# omnetics_to_electrode.net
KiCad netlist of a schematic drawn in EAGLE
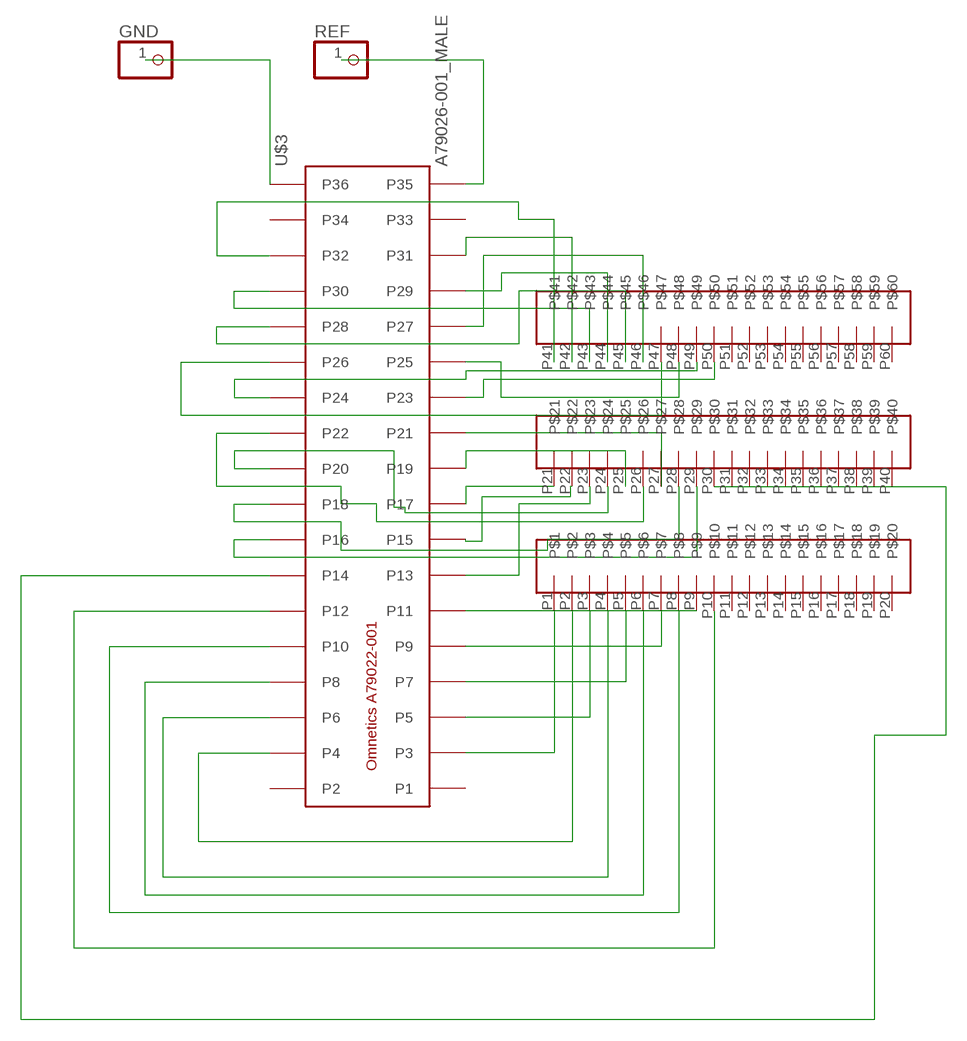
[diagram p0: schematic, sheet 1]

(export (version "E")
  (design (tool "Eeschema 10.0.6"))
  (components
    (comp (ref "GND")
      (value "PINHD-1X1")
      (footprint "eagle-import:1X01")
      (libsource (lib "eagle-import") (part "PINHD-1X1"))
    )
    (comp (ref "REF")
      (value "PINHD-1X1")
      (footprint "eagle-import:1X01")
      (libsource (lib "eagle-import") (part "PINHD-1X1"))
    )
    (comp (ref "U$1")
      (value "ELEC_CONNECTOR")
      (footprint "eagle-import:ELEC_CONNECTOR")
      (libsource (lib "eagle-import") (part "ELEC_CONNECTOR"))
    )
    (comp (ref "U$3")
      (value "A79026-001_MALE")
      (footprint "eagle-import:A79026-001_MALE")
      (libsource (lib "eagle-import") (part "A79026-001_MALE"))
    )
  )
  (nets
    (net (code "1") (name "Net-(GND-Pad1)") (class "Default")
      (node (ref "GND") (pin "1") (pinfunction "1_1") (pintype "passive"))
      (node (ref "U$3") (pin "P36") (pinfunction "P36_P36") (pintype "bidirectional"))
    )
    (net (code "2") (name "Net-(REF-Pad1)") (class "Default")
      (node (ref "REF") (pin "1") (pinfunction "1_1") (pintype "passive"))
      (node (ref "U$3") (pin "P35") (pinfunction "P35_P35") (pintype "bidirectional"))
    )
    (net (code "3") (name "Net-(U$1-P$1)") (class "Default")
      (node (ref "U$1") (pin "P1") (pinfunction "P$1_P1") (pintype "bidirectional"))
      (node (ref "U$3") (pin "P3") (pinfunction "P3_P3") (pintype "bidirectional"))
    )
    (net (code "4") (name "Net-(U$1-P$2)") (class "Default")
      (node (ref "U$1") (pin "P2") (pinfunction "P$2_P2") (pintype "bidirectional"))
      (node (ref "U$3") (pin "P4") (pinfunction "P4_P4") (pintype "bidirectional"))
    )
    (net (code "5") (name "Net-(U$1-P$3)") (class "Default")
      (node (ref "U$1") (pin "P3") (pinfunction "P$3_P3") (pintype "bidirectional"))
      (node (ref "U$3") (pin "P5") (pinfunction "P5_P5") (pintype "bidirectional"))
    )
    (net (code "6") (name "Net-(U$1-P$4)") (class "Default")
      (node (ref "U$1") (pin "P4") (pinfunction "P$4_P4") (pintype "bidirectional"))
      (node (ref "U$3") (pin "P6") (pinfunction "P6_P6") (pintype "bidirectional"))
    )
    (net (code "7") (name "Net-(U$1-P$5)") (class "Default")
      (node (ref "U$1") (pin "P5") (pinfunction "P$5_P5") (pintype "bidirectional"))
      (node (ref "U$3") (pin "P7") (pinfunction "P7_P7") (pintype "bidirectional"))
    )
    (net (code "8") (name "Net-(U$1-P$6)") (class "Default")
      (node (ref "U$1") (pin "P6") (pinfunction "P$6_P6") (pintype "bidirectional"))
      (node (ref "U$3") (pin "P8") (pinfunction "P8_P8") (pintype "bidirectional"))
    )
    (net (code "9") (name "Net-(U$1-P$7)") (class "Default")
      (node (ref "U$1") (pin "P7") (pinfunction "P$7_P7") (pintype "bidirectional"))
      (node (ref "U$3") (pin "P9") (pinfunction "P9_P9") (pintype "bidirectional"))
    )
    (net (code "10") (name "Net-(U$1-P$8)") (class "Default")
      (node (ref "U$1") (pin "P8") (pinfunction "P$8_P8") (pintype "bidirectional"))
      (node (ref "U$3") (pin "P10") (pinfunction "P10_P10") (pintype "bidirectional"))
    )
    (net (code "11") (name "Net-(U$1-P$9)") (class "Default")
      (node (ref "U$1") (pin "P9") (pinfunction "P$9_P9") (pintype "bidirectional"))
      (node (ref "U$3") (pin "P11") (pinfunction "P11_P11") (pintype "bidirectional"))
    )
    (net (code "12") (name "Net-(U$1-P$10)") (class "Default")
      (node (ref "U$1") (pin "P10") (pinfunction "P$10_P10") (pintype "bidirectional"))
      (node (ref "U$3") (pin "P12") (pinfunction "P12_P12") (pintype "bidirectional"))
    )
    (net (code "13") (name "Net-(U$1-P$21)") (class "Default")
      (node (ref "U$1") (pin "P21") (pinfunction "P$21_P21") (pintype "bidirectional"))
      (node (ref "U$3") (pin "P17") (pinfunction "P17_P17") (pintype "bidirectional"))
    )
    (net (code "14") (name "Net-(U$1-P$22)") (class "Default")
      (node (ref "U$1") (pin "P22") (pinfunction "P$22_P22") (pintype "bidirectional"))
      (node (ref "U$3") (pin "P15") (pinfunction "P15_P15") (pintype "bidirectional"))
    )
    (net (code "15") (name "Net-(U$1-P$23)") (class "Default")
      (node (ref "U$1") (pin "P23") (pinfunction "P$23_P23") (pintype "bidirectional"))
      (node (ref "U$3") (pin "P13") (pinfunction "P13_P13") (pintype "bidirectional"))
    )
    (net (code "16") (name "Net-(U$1-P$24)") (class "Default")
      (node (ref "U$1") (pin "P24") (pinfunction "P$24_P24") (pintype "bidirectional"))
      (node (ref "U$3") (pin "P20") (pinfunction "P20_P20") (pintype "bidirectional"))
    )
    (net (code "17") (name "Net-(U$1-P$25)") (class "Default")
      (node (ref "U$1") (pin "P25") (pinfunction "P$25_P25") (pintype "bidirectional"))
      (node (ref "U$3") (pin "P19") (pinfunction "P19_P19") (pintype "bidirectional"))
    )
    (net (code "18") (name "Net-(U$1-P$26)") (class "Default")
      (node (ref "U$1") (pin "P26") (pinfunction "P$26_P26") (pintype "bidirectional"))
      (node (ref "U$3") (pin "P22") (pinfunction "P22_P22") (pintype "bidirectional"))
    )
    (net (code "19") (name "Net-(U$1-P$27)") (class "Default")
      (node (ref "U$1") (pin "P27") (pinfunction "P$27_P27") (pintype "bidirectional"))
      (node (ref "U$3") (pin "P21") (pinfunction "P21_P21") (pintype "bidirectional"))
    )
    (net (code "20") (name "Net-(U$1-P$28)") (class "Default")
      (node (ref "U$1") (pin "P28") (pinfunction "P$28_P28") (pintype "bidirectional"))
      (node (ref "U$3") (pin "P18") (pinfunction "P18_P18") (pintype "bidirectional"))
    )
    (net (code "21") (name "Net-(U$1-P$29)") (class "Default")
      (node (ref "U$1") (pin "P29") (pinfunction "P$29_P29") (pintype "bidirectional"))
      (node (ref "U$3") (pin "P16") (pinfunction "P16_P16") (pintype "bidirectional"))
    )
    (net (code "22") (name "Net-(U$1-P$30)") (class "Default")
      (node (ref "U$1") (pin "P30") (pinfunction "P$30_P30") (pintype "bidirectional"))
      (node (ref "U$3") (pin "P14") (pinfunction "P14_P14") (pintype "bidirectional"))
    )
    (net (code "23") (name "Net-(U$1-P$41)") (class "Default")
      (node (ref "U$1") (pin "P41") (pinfunction "P$41_P41") (pintype "bidirectional"))
      (node (ref "U$3") (pin "P32") (pinfunction "P32_P32") (pintype "bidirectional"))
    )
    (net (code "24") (name "Net-(U$1-P$42)") (class "Default")
      (node (ref "U$1") (pin "P42") (pinfunction "P$42_P42") (pintype "bidirectional"))
      (node (ref "U$3") (pin "P31") (pinfunction "P31_P31") (pintype "bidirectional"))
    )
    (net (code "25") (name "Net-(U$1-P$43)") (class "Default")
      (node (ref "U$1") (pin "P43") (pinfunction "P$43_P43") (pintype "bidirectional"))
      (node (ref "U$3") (pin "P30") (pinfunction "P30_P30") (pintype "bidirectional"))
    )
    (net (code "26") (name "Net-(U$1-P$44)") (class "Default")
      (node (ref "U$1") (pin "P44") (pinfunction "P$44_P44") (pintype "bidirectional"))
      (node (ref "U$3") (pin "P29") (pinfunction "P29_P29") (pintype "bidirectional"))
    )
    (net (code "27") (name "Net-(U$1-P$45)") (class "Default")
      (node (ref "U$1") (pin "P45") (pinfunction "P$45_P45") (pintype "bidirectional"))
      (node (ref "U$3") (pin "P28") (pinfunction "P28_P28") (pintype "bidirectional"))
    )
    (net (code "28") (name "Net-(U$1-P$46)") (class "Default")
      (node (ref "U$1") (pin "P46") (pinfunction "P$46_P46") (pintype "bidirectional"))
      (node (ref "U$3") (pin "P27") (pinfunction "P27_P27") (pintype "bidirectional"))
    )
    (net (code "29") (name "Net-(U$1-P$47)") (class "Default")
      (node (ref "U$1") (pin "P47") (pinfunction "P$47_P47") (pintype "bidirectional"))
      (node (ref "U$3") (pin "P26") (pinfunction "P26_P26") (pintype "bidirectional"))
    )
    (net (code "30") (name "Net-(U$1-P$48)") (class "Default")
      (node (ref "U$1") (pin "P48") (pinfunction "P$48_P48") (pintype "bidirectional"))
      (node (ref "U$3") (pin "P25") (pinfunction "P25_P25") (pintype "bidirectional"))
    )
    (net (code "31") (name "Net-(U$1-P$49)") (class "Default")
      (node (ref "U$1") (pin "P49") (pinfunction "P$49_P49") (pintype "bidirectional"))
      (node (ref "U$3") (pin "P24") (pinfunction "P24_P24") (pintype "bidirectional"))
    )
    (net (code "32") (name "Net-(U$1-P$50)") (class "Default")
      (node (ref "U$1") (pin "P50") (pinfunction "P$50_P50") (pintype "bidirectional"))
      (node (ref "U$3") (pin "P23") (pinfunction "P23_P23") (pintype "bidirectional"))
    )
    (net (code "33") (name "unconnected-(U$1-P$11-PadP11)") (class "Default")
      (node (ref "U$1") (pin "P11") (pinfunction "P$11_P11") (pintype "bidirectional"))
    )
    (net (code "34") (name "unconnected-(U$1-P$12-PadP12)") (class "Default")
      (node (ref "U$1") (pin "P12") (pinfunction "P$12_P12") (pintype "bidirectional"))
    )
    (net (code "35") (name "unconnected-(U$1-P$13-PadP13)") (class "Default")
      (node (ref "U$1") (pin "P13") (pinfunction "P$13_P13") (pintype "bidirectional"))
    )
    (net (code "36") (name "unconnected-(U$1-P$14-PadP14)") (class "Default")
      (node (ref "U$1") (pin "P14") (pinfunction "P$14_P14") (pintype "bidirectional"))
    )
    (net (code "37") (name "unconnected-(U$1-P$15-PadP15)") (class "Default")
      (node (ref "U$1") (pin "P15") (pinfunction "P$15_P15") (pintype "bidirectional"))
    )
    (net (code "38") (name "unconnected-(U$1-P$16-PadP16)") (class "Default")
      (node (ref "U$1") (pin "P16") (pinfunction "P$16_P16") (pintype "bidirectional"))
    )
    (net (code "39") (name "unconnected-(U$1-P$17-PadP17)") (class "Default")
      (node (ref "U$1") (pin "P17") (pinfunction "P$17_P17") (pintype "bidirectional"))
    )
    (net (code "40") (name "unconnected-(U$1-P$18-PadP18)") (class "Default")
      (node (ref "U$1") (pin "P18") (pinfunction "P$18_P18") (pintype "bidirectional"))
    )
    (net (code "41") (name "unconnected-(U$1-P$19-PadP19)") (class "Default")
      (node (ref "U$1") (pin "P19") (pinfunction "P$19_P19") (pintype "bidirectional"))
    )
    (net (code "42") (name "unconnected-(U$1-P$20-PadP20)") (class "Default")
      (node (ref "U$1") (pin "P20") (pinfunction "P$20_P20") (pintype "bidirectional"))
    )
    (net (code "43") (name "unconnected-(U$1-P$31-PadP31)") (class "Default")
      (node (ref "U$1") (pin "P31") (pinfunction "P$31_P31") (pintype "bidirectional"))
    )
    (net (code "44") (name "unconnected-(U$1-P$32-PadP32)") (class "Default")
      (node (ref "U$1") (pin "P32") (pinfunction "P$32_P32") (pintype "bidirectional"))
    )
    (net (code "45") (name "unconnected-(U$1-P$33-PadP33)") (class "Default")
      (node (ref "U$1") (pin "P33") (pinfunction "P$33_P33") (pintype "bidirectional"))
    )
    (net (code "46") (name "unconnected-(U$1-P$34-PadP34)") (class "Default")
      (node (ref "U$1") (pin "P34") (pinfunction "P$34_P34") (pintype "bidirectional"))
    )
    (net (code "47") (name "unconnected-(U$1-P$35-PadP35)") (class "Default")
      (node (ref "U$1") (pin "P35") (pinfunction "P$35_P35") (pintype "bidirectional"))
    )
    (net (code "48") (name "unconnected-(U$1-P$36-PadP36)") (class "Default")
      (node (ref "U$1") (pin "P36") (pinfunction "P$36_P36") (pintype "bidirectional"))
    )
    (net (code "49") (name "unconnected-(U$1-P$37-PadP37)") (class "Default")
      (node (ref "U$1") (pin "P37") (pinfunction "P$37_P37") (pintype "bidirectional"))
    )
    (net (code "50") (name "unconnected-(U$1-P$38-PadP38)") (class "Default")
      (node (ref "U$1") (pin "P38") (pinfunction "P$38_P38") (pintype "bidirectional"))
    )
    (net (code "51") (name "unconnected-(U$1-P$39-PadP39)") (class "Default")
      (node (ref "U$1") (pin "P39") (pinfunction "P$39_P39") (pintype "bidirectional"))
    )
    (net (code "52") (name "unconnected-(U$1-P$40-PadP40)") (class "Default")
      (node (ref "U$1") (pin "P40") (pinfunction "P$40_P40") (pintype "bidirectional"))
    )
    (net (code "53") (name "unconnected-(U$1-P$51-PadP51)") (class "Default")
      (node (ref "U$1") (pin "P51") (pinfunction "P$51_P51") (pintype "bidirectional"))
    )
    (net (code "54") (name "unconnected-(U$1-P$52-PadP52)") (class "Default")
      (node (ref "U$1") (pin "P52") (pinfunction "P$52_P52") (pintype "bidirectional"))
    )
    (net (code "55") (name "unconnected-(U$1-P$53-PadP53)") (class "Default")
      (node (ref "U$1") (pin "P53") (pinfunction "P$53_P53") (pintype "bidirectional"))
    )
    (net (code "56") (name "unconnected-(U$1-P$54-PadP54)") (class "Default")
      (node (ref "U$1") (pin "P54") (pinfunction "P$54_P54") (pintype "bidirectional"))
    )
    (net (code "57") (name "unconnected-(U$1-P$55-PadP55)") (class "Default")
      (node (ref "U$1") (pin "P55") (pinfunction "P$55_P55") (pintype "bidirectional"))
    )
    (net (code "58") (name "unconnected-(U$1-P$56-PadP56)") (class "Default")
      (node (ref "U$1") (pin "P56") (pinfunction "P$56_P56") (pintype "bidirectional"))
    )
    (net (code "59") (name "unconnected-(U$1-P$57-PadP57)") (class "Default")
      (node (ref "U$1") (pin "P57") (pinfunction "P$57_P57") (pintype "bidirectional"))
    )
    (net (code "60") (name "unconnected-(U$1-P$58-PadP58)") (class "Default")
      (node (ref "U$1") (pin "P58") (pinfunction "P$58_P58") (pintype "bidirectional"))
    )
    (net (code "61") (name "unconnected-(U$1-P$59-PadP59)") (class "Default")
      (node (ref "U$1") (pin "P59") (pinfunction "P$59_P59") (pintype "bidirectional"))
    )
    (net (code "62") (name "unconnected-(U$1-P$60-PadP60)") (class "Default")
      (node (ref "U$1") (pin "P60") (pinfunction "P$60_P60") (pintype "bidirectional"))
    )
    (net (code "63") (name "unconnected-(U$3-PadP1)") (class "Default")
      (node (ref "U$3") (pin "P1") (pinfunction "P1_P1") (pintype "bidirectional"))
    )
    (net (code "64") (name "unconnected-(U$3-PadP2)") (class "Default")
      (node (ref "U$3") (pin "P2") (pinfunction "P2_P2") (pintype "bidirectional"))
    )
    (net (code "65") (name "unconnected-(U$3-PadP33)") (class "Default")
      (node (ref "U$3") (pin "P33") (pinfunction "P33_P33") (pintype "bidirectional"))
    )
    (net (code "66") (name "unconnected-(U$3-PadP34)") (class "Default")
      (node (ref "U$3") (pin "P34") (pinfunction "P34_P34") (pintype "bidirectional"))
    )
  )
)
